# chart3.net
KiCad netlist of a schematic drawn in EAGLE
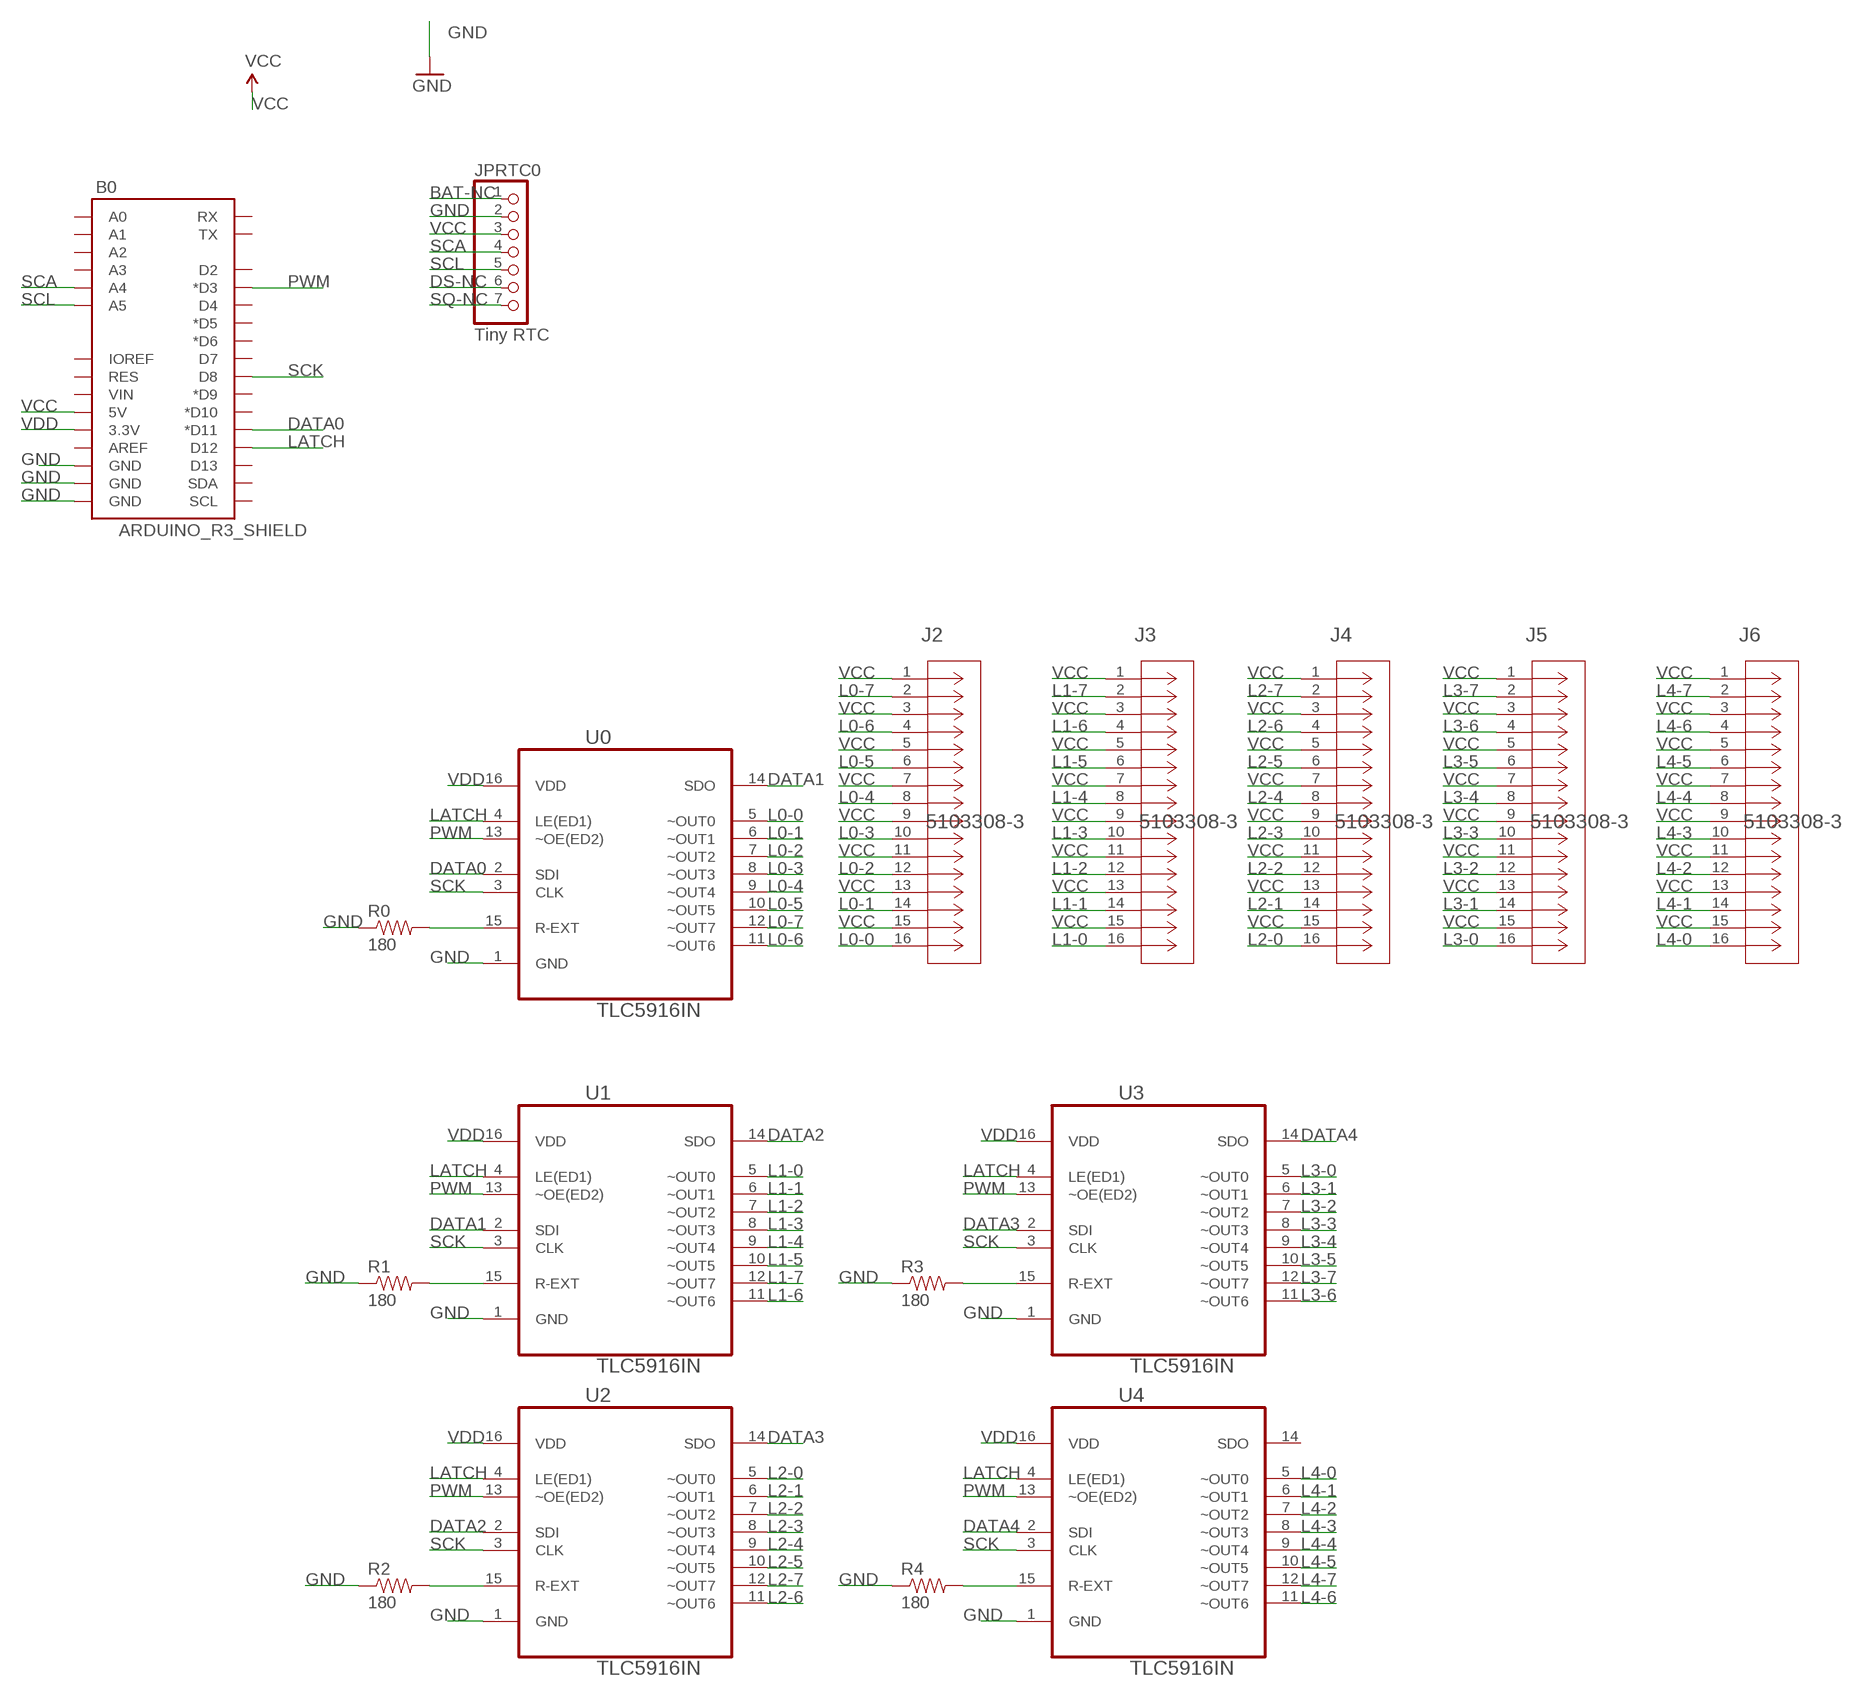
[diagram p0: schematic, sheet 1]

(export (version "E")
  (design (tool "Eeschema 10.0.6"))
  (components
    (comp (ref "B0")
      (value "ARDUINO_R3_SHIELD")
      (footprint "eagle-import:UNO_R3_SHIELD")
      (libsource (lib "eagle-import") (part "ARDUINO_R3_SHIELD"))
    )
    (comp (ref "J2")
      (value "5103308-3")
      (footprint "eagle-import:CON16_2X8_S4")
      (fields
        (field (name "DIGIKEYPARTNUMBER") "A33163-ND")
        (field (name "COPYRIGHT") "Copyright (C) 2015 Accelerated Designs. All rights reserved")
      )
      (libsource (lib "eagle-import") (part "5103308-3"))
    )
    (comp (ref "J3")
      (value "5103308-3")
      (footprint "eagle-import:CON16_2X8_S4")
      (fields
        (field (name "DIGIKEYPARTNUMBER") "A33163-ND")
        (field (name "COPYRIGHT") "Copyright (C) 2015 Accelerated Designs. All rights reserved")
      )
      (libsource (lib "eagle-import") (part "5103308-3"))
    )
    (comp (ref "J4")
      (value "5103308-3")
      (footprint "eagle-import:CON16_2X8_S4")
      (fields
        (field (name "DIGIKEYPARTNUMBER") "A33163-ND")
        (field (name "COPYRIGHT") "Copyright (C) 2015 Accelerated Designs. All rights reserved")
      )
      (libsource (lib "eagle-import") (part "5103308-3"))
    )
    (comp (ref "J5")
      (value "5103308-3")
      (footprint "eagle-import:CON16_2X8_S4")
      (fields
        (field (name "DIGIKEYPARTNUMBER") "A33163-ND")
        (field (name "COPYRIGHT") "Copyright (C) 2015 Accelerated Designs. All rights reserved")
      )
      (libsource (lib "eagle-import") (part "5103308-3"))
    )
    (comp (ref "J6")
      (value "5103308-3")
      (footprint "eagle-import:CON16_2X8_S4")
      (fields
        (field (name "DIGIKEYPARTNUMBER") "A33163-ND")
        (field (name "COPYRIGHT") "Copyright (C) 2015 Accelerated Designs. All rights reserved")
      )
      (libsource (lib "eagle-import") (part "5103308-3"))
    )
    (comp (ref "JPRTC0")
      (value "Tiny RTC")
      (footprint "eagle-import:1X07")
      (libsource (lib "eagle-import") (part "PINHD-1X7"))
    )
    (comp (ref "R0")
      (value "180")
      (footprint "eagle-import:AXIAL-0.4")
      (libsource (lib "eagle-import") (part "RESISTORPTH-1/4W"))
    )
    (comp (ref "R1")
      (value "180")
      (footprint "eagle-import:AXIAL-0.4")
      (libsource (lib "eagle-import") (part "RESISTORPTH-1/4W"))
    )
    (comp (ref "R2")
      (value "180")
      (footprint "eagle-import:AXIAL-0.4")
      (libsource (lib "eagle-import") (part "RESISTORPTH-1/4W"))
    )
    (comp (ref "R3")
      (value "180")
      (footprint "eagle-import:AXIAL-0.4")
      (libsource (lib "eagle-import") (part "RESISTORPTH-1/4W"))
    )
    (comp (ref "R4")
      (value "180")
      (footprint "eagle-import:AXIAL-0.4")
      (libsource (lib "eagle-import") (part "RESISTORPTH-1/4W"))
    )
    (comp (ref "U0")
      (value "TLC5916IN")
      (footprint "eagle-import:DIP254P762X508-16")
      (libsource (lib "eagle-import") (part "TLC5916IN"))
    )
    (comp (ref "U1")
      (value "TLC5916IN")
      (footprint "eagle-import:DIP254P762X508-16")
      (libsource (lib "eagle-import") (part "TLC5916IN"))
    )
    (comp (ref "U2")
      (value "TLC5916IN")
      (footprint "eagle-import:DIP254P762X508-16")
      (libsource (lib "eagle-import") (part "TLC5916IN"))
    )
    (comp (ref "U3")
      (value "TLC5916IN")
      (footprint "eagle-import:DIP254P762X508-16")
      (libsource (lib "eagle-import") (part "TLC5916IN"))
    )
    (comp (ref "U4")
      (value "TLC5916IN")
      (footprint "eagle-import:DIP254P762X508-16")
      (libsource (lib "eagle-import") (part "TLC5916IN"))
    )
  )
  (nets
    (net (code "1") (name "/BAT-NC") (class "Default")
      (node (ref "JPRTC0") (pin "1") (pinfunction "1_1") (pintype "passive"))
    )
    (net (code "2") (name "/DATA0") (class "Default")
      (node (ref "B0") (pin "D11") (pinfunction "*D11_D11") (pintype "bidirectional"))
      (node (ref "U0") (pin "2") (pinfunction "SDI_2") (pintype "input"))
    )
    (net (code "3") (name "/DATA1") (class "Default")
      (node (ref "U0") (pin "14") (pinfunction "SDO_14") (pintype "output"))
      (node (ref "U1") (pin "2") (pinfunction "SDI_2") (pintype "input"))
    )
    (net (code "4") (name "/DATA2") (class "Default")
      (node (ref "U1") (pin "14") (pinfunction "SDO_14") (pintype "output"))
      (node (ref "U2") (pin "2") (pinfunction "SDI_2") (pintype "input"))
    )
    (net (code "5") (name "/DATA3") (class "Default")
      (node (ref "U2") (pin "14") (pinfunction "SDO_14") (pintype "output"))
      (node (ref "U3") (pin "2") (pinfunction "SDI_2") (pintype "input"))
    )
    (net (code "6") (name "/DATA4") (class "Default")
      (node (ref "U3") (pin "14") (pinfunction "SDO_14") (pintype "output"))
      (node (ref "U4") (pin "2") (pinfunction "SDI_2") (pintype "input"))
    )
    (net (code "7") (name "/DS-NC") (class "Default")
      (node (ref "JPRTC0") (pin "6") (pinfunction "6_6") (pintype "passive"))
    )
    (net (code "8") (name "/L0-0") (class "Default")
      (node (ref "J2") (pin "16") (pinfunction "16_16") (pintype "passive"))
      (node (ref "U0") (pin "5") (pinfunction "~{OUT0}_5") (pintype "output"))
    )
    (net (code "9") (name "/L0-1") (class "Default")
      (node (ref "J2") (pin "14") (pinfunction "14_14") (pintype "passive"))
      (node (ref "U0") (pin "6") (pinfunction "~{OUT1}_6") (pintype "output"))
    )
    (net (code "10") (name "/L0-2") (class "Default")
      (node (ref "J2") (pin "12") (pinfunction "12_12") (pintype "passive"))
      (node (ref "U0") (pin "7") (pinfunction "~{OUT2}_7") (pintype "output"))
    )
    (net (code "11") (name "/L0-3") (class "Default")
      (node (ref "J2") (pin "10") (pinfunction "10_10") (pintype "passive"))
      (node (ref "U0") (pin "8") (pinfunction "~{OUT3}_8") (pintype "output"))
    )
    (net (code "12") (name "/L0-4") (class "Default")
      (node (ref "J2") (pin "8") (pinfunction "8_8") (pintype "passive"))
      (node (ref "U0") (pin "9") (pinfunction "~{OUT4}_9") (pintype "output"))
    )
    (net (code "13") (name "/L0-5") (class "Default")
      (node (ref "J2") (pin "6") (pinfunction "6_6") (pintype "passive"))
      (node (ref "U0") (pin "10") (pinfunction "~{OUT5}_10") (pintype "output"))
    )
    (net (code "14") (name "/L0-6") (class "Default")
      (node (ref "J2") (pin "4") (pinfunction "4_4") (pintype "passive"))
      (node (ref "U0") (pin "11") (pinfunction "~{OUT6}_11") (pintype "output"))
    )
    (net (code "15") (name "/L0-7") (class "Default")
      (node (ref "J2") (pin "2") (pinfunction "2_2") (pintype "passive"))
      (node (ref "U0") (pin "12") (pinfunction "~{OUT7}_12") (pintype "output"))
    )
    (net (code "16") (name "/L1-0") (class "Default")
      (node (ref "J3") (pin "16") (pinfunction "16_16") (pintype "passive"))
      (node (ref "U1") (pin "5") (pinfunction "~{OUT0}_5") (pintype "output"))
    )
    (net (code "17") (name "/L1-1") (class "Default")
      (node (ref "J3") (pin "14") (pinfunction "14_14") (pintype "passive"))
      (node (ref "U1") (pin "6") (pinfunction "~{OUT1}_6") (pintype "output"))
    )
    (net (code "18") (name "/L1-2") (class "Default")
      (node (ref "J3") (pin "12") (pinfunction "12_12") (pintype "passive"))
      (node (ref "U1") (pin "7") (pinfunction "~{OUT2}_7") (pintype "output"))
    )
    (net (code "19") (name "/L1-3") (class "Default")
      (node (ref "J3") (pin "10") (pinfunction "10_10") (pintype "passive"))
      (node (ref "U1") (pin "8") (pinfunction "~{OUT3}_8") (pintype "output"))
    )
    (net (code "20") (name "/L1-4") (class "Default")
      (node (ref "J3") (pin "8") (pinfunction "8_8") (pintype "passive"))
      (node (ref "U1") (pin "9") (pinfunction "~{OUT4}_9") (pintype "output"))
    )
    (net (code "21") (name "/L1-5") (class "Default")
      (node (ref "J3") (pin "6") (pinfunction "6_6") (pintype "passive"))
      (node (ref "U1") (pin "10") (pinfunction "~{OUT5}_10") (pintype "output"))
    )
    (net (code "22") (name "/L1-6") (class "Default")
      (node (ref "J3") (pin "4") (pinfunction "4_4") (pintype "passive"))
      (node (ref "U1") (pin "11") (pinfunction "~{OUT6}_11") (pintype "output"))
    )
    (net (code "23") (name "/L1-7") (class "Default")
      (node (ref "J3") (pin "2") (pinfunction "2_2") (pintype "passive"))
      (node (ref "U1") (pin "12") (pinfunction "~{OUT7}_12") (pintype "output"))
    )
    (net (code "24") (name "/L2-0") (class "Default")
      (node (ref "J4") (pin "16") (pinfunction "16_16") (pintype "passive"))
      (node (ref "U2") (pin "5") (pinfunction "~{OUT0}_5") (pintype "output"))
    )
    (net (code "25") (name "/L2-1") (class "Default")
      (node (ref "J4") (pin "14") (pinfunction "14_14") (pintype "passive"))
      (node (ref "U2") (pin "6") (pinfunction "~{OUT1}_6") (pintype "output"))
    )
    (net (code "26") (name "/L2-2") (class "Default")
      (node (ref "J4") (pin "12") (pinfunction "12_12") (pintype "passive"))
      (node (ref "U2") (pin "7") (pinfunction "~{OUT2}_7") (pintype "output"))
    )
    (net (code "27") (name "/L2-3") (class "Default")
      (node (ref "J4") (pin "10") (pinfunction "10_10") (pintype "passive"))
      (node (ref "U2") (pin "8") (pinfunction "~{OUT3}_8") (pintype "output"))
    )
    (net (code "28") (name "/L2-4") (class "Default")
      (node (ref "J4") (pin "8") (pinfunction "8_8") (pintype "passive"))
      (node (ref "U2") (pin "9") (pinfunction "~{OUT4}_9") (pintype "output"))
    )
    (net (code "29") (name "/L2-5") (class "Default")
      (node (ref "J4") (pin "6") (pinfunction "6_6") (pintype "passive"))
      (node (ref "U2") (pin "10") (pinfunction "~{OUT5}_10") (pintype "output"))
    )
    (net (code "30") (name "/L2-6") (class "Default")
      (node (ref "J4") (pin "4") (pinfunction "4_4") (pintype "passive"))
      (node (ref "U2") (pin "11") (pinfunction "~{OUT6}_11") (pintype "output"))
    )
    (net (code "31") (name "/L2-7") (class "Default")
      (node (ref "J4") (pin "2") (pinfunction "2_2") (pintype "passive"))
      (node (ref "U2") (pin "12") (pinfunction "~{OUT7}_12") (pintype "output"))
    )
    (net (code "32") (name "/L3-0") (class "Default")
      (node (ref "J5") (pin "16") (pinfunction "16_16") (pintype "passive"))
      (node (ref "U3") (pin "5") (pinfunction "~{OUT0}_5") (pintype "output"))
    )
    (net (code "33") (name "/L3-1") (class "Default")
      (node (ref "J5") (pin "14") (pinfunction "14_14") (pintype "passive"))
      (node (ref "U3") (pin "6") (pinfunction "~{OUT1}_6") (pintype "output"))
    )
    (net (code "34") (name "/L3-2") (class "Default")
      (node (ref "J5") (pin "12") (pinfunction "12_12") (pintype "passive"))
      (node (ref "U3") (pin "7") (pinfunction "~{OUT2}_7") (pintype "output"))
    )
    (net (code "35") (name "/L3-3") (class "Default")
      (node (ref "J5") (pin "10") (pinfunction "10_10") (pintype "passive"))
      (node (ref "U3") (pin "8") (pinfunction "~{OUT3}_8") (pintype "output"))
    )
    (net (code "36") (name "/L3-4") (class "Default")
      (node (ref "J5") (pin "8") (pinfunction "8_8") (pintype "passive"))
      (node (ref "U3") (pin "9") (pinfunction "~{OUT4}_9") (pintype "output"))
    )
    (net (code "37") (name "/L3-5") (class "Default")
      (node (ref "J5") (pin "6") (pinfunction "6_6") (pintype "passive"))
      (node (ref "U3") (pin "10") (pinfunction "~{OUT5}_10") (pintype "output"))
    )
    (net (code "38") (name "/L3-6") (class "Default")
      (node (ref "J5") (pin "4") (pinfunction "4_4") (pintype "passive"))
      (node (ref "U3") (pin "11") (pinfunction "~{OUT6}_11") (pintype "output"))
    )
    (net (code "39") (name "/L3-7") (class "Default")
      (node (ref "J5") (pin "2") (pinfunction "2_2") (pintype "passive"))
      (node (ref "U3") (pin "12") (pinfunction "~{OUT7}_12") (pintype "output"))
    )
    (net (code "40") (name "/L4-0") (class "Default")
      (node (ref "J6") (pin "16") (pinfunction "16_16") (pintype "passive"))
      (node (ref "U4") (pin "5") (pinfunction "~{OUT0}_5") (pintype "output"))
    )
    (net (code "41") (name "/L4-1") (class "Default")
      (node (ref "J6") (pin "14") (pinfunction "14_14") (pintype "passive"))
      (node (ref "U4") (pin "6") (pinfunction "~{OUT1}_6") (pintype "output"))
    )
    (net (code "42") (name "/L4-2") (class "Default")
      (node (ref "J6") (pin "12") (pinfunction "12_12") (pintype "passive"))
      (node (ref "U4") (pin "7") (pinfunction "~{OUT2}_7") (pintype "output"))
    )
    (net (code "43") (name "/L4-3") (class "Default")
      (node (ref "J6") (pin "10") (pinfunction "10_10") (pintype "passive"))
      (node (ref "U4") (pin "8") (pinfunction "~{OUT3}_8") (pintype "output"))
    )
    (net (code "44") (name "/L4-4") (class "Default")
      (node (ref "J6") (pin "8") (pinfunction "8_8") (pintype "passive"))
      (node (ref "U4") (pin "9") (pinfunction "~{OUT4}_9") (pintype "output"))
    )
    (net (code "45") (name "/L4-5") (class "Default")
      (node (ref "J6") (pin "6") (pinfunction "6_6") (pintype "passive"))
      (node (ref "U4") (pin "10") (pinfunction "~{OUT5}_10") (pintype "output"))
    )
    (net (code "46") (name "/L4-6") (class "Default")
      (node (ref "J6") (pin "4") (pinfunction "4_4") (pintype "passive"))
      (node (ref "U4") (pin "11") (pinfunction "~{OUT6}_11") (pintype "output"))
    )
    (net (code "47") (name "/L4-7") (class "Default")
      (node (ref "J6") (pin "2") (pinfunction "2_2") (pintype "passive"))
      (node (ref "U4") (pin "12") (pinfunction "~{OUT7}_12") (pintype "output"))
    )
    (net (code "48") (name "/LATCH") (class "Default")
      (node (ref "B0") (pin "D12") (pinfunction "D12_D12") (pintype "bidirectional"))
      (node (ref "U0") (pin "4") (pinfunction "LE(ED1)_4") (pintype "input"))
      (node (ref "U1") (pin "4") (pinfunction "LE(ED1)_4") (pintype "input"))
      (node (ref "U2") (pin "4") (pinfunction "LE(ED1)_4") (pintype "input"))
      (node (ref "U3") (pin "4") (pinfunction "LE(ED1)_4") (pintype "input"))
      (node (ref "U4") (pin "4") (pinfunction "LE(ED1)_4") (pintype "input"))
    )
    (net (code "49") (name "/PWM") (class "Default")
      (node (ref "B0") (pin "D3") (pinfunction "*D3_D3") (pintype "bidirectional"))
      (node (ref "U0") (pin "13") (pinfunction "~{OE(ED2})_13") (pintype "input"))
      (node (ref "U1") (pin "13") (pinfunction "~{OE(ED2})_13") (pintype "input"))
      (node (ref "U2") (pin "13") (pinfunction "~{OE(ED2})_13") (pintype "input"))
      (node (ref "U3") (pin "13") (pinfunction "~{OE(ED2})_13") (pintype "input"))
      (node (ref "U4") (pin "13") (pinfunction "~{OE(ED2})_13") (pintype "input"))
    )
    (net (code "50") (name "/SCA") (class "Default")
      (node (ref "B0") (pin "A4") (pinfunction "A4_A4") (pintype "bidirectional"))
      (node (ref "JPRTC0") (pin "4") (pinfunction "4_4") (pintype "passive"))
    )
    (net (code "51") (name "/SCK") (class "Default")
      (node (ref "B0") (pin "D8") (pinfunction "D8_D8") (pintype "bidirectional"))
      (node (ref "U0") (pin "3") (pinfunction "CLK_3") (pintype "input"))
      (node (ref "U1") (pin "3") (pinfunction "CLK_3") (pintype "input"))
      (node (ref "U2") (pin "3") (pinfunction "CLK_3") (pintype "input"))
      (node (ref "U3") (pin "3") (pinfunction "CLK_3") (pintype "input"))
      (node (ref "U4") (pin "3") (pinfunction "CLK_3") (pintype "input"))
    )
    (net (code "52") (name "/SCL") (class "Default")
      (node (ref "B0") (pin "A5") (pinfunction "A5_A5") (pintype "bidirectional"))
      (node (ref "JPRTC0") (pin "5") (pinfunction "5_5") (pintype "passive"))
    )
    (net (code "53") (name "/SQ-NC") (class "Default")
      (node (ref "JPRTC0") (pin "7") (pinfunction "7_7") (pintype "passive"))
    )
    (net (code "54") (name "/VDD") (class "Default")
      (node (ref "B0") (pin "3.3V") (pinfunction "3.3V_3.3V") (pintype "bidirectional"))
      (node (ref "U0") (pin "16") (pinfunction "VDD_16") (pintype "power_in"))
      (node (ref "U1") (pin "16") (pinfunction "VDD_16") (pintype "power_in"))
      (node (ref "U2") (pin "16") (pinfunction "VDD_16") (pintype "power_in"))
      (node (ref "U3") (pin "16") (pinfunction "VDD_16") (pintype "power_in"))
      (node (ref "U4") (pin "16") (pinfunction "VDD_16") (pintype "power_in"))
    )
    (net (code "55") (name "GND") (class "Default")
      (node (ref "B0") (pin "GND@0") (pinfunction "GND_GND@0") (pintype "bidirectional"))
      (node (ref "B0") (pin "GND@1") (pinfunction "GND_GND@1") (pintype "bidirectional"))
      (node (ref "B0") (pin "GND@2") (pinfunction "GND_GND@2") (pintype "bidirectional"))
      (node (ref "JPRTC0") (pin "2") (pinfunction "2_2") (pintype "passive"))
      (node (ref "R0") (pin "P$1") (pinfunction "1_P$1") (pintype "passive"))
      (node (ref "R1") (pin "P$1") (pinfunction "1_P$1") (pintype "passive"))
      (node (ref "R2") (pin "P$1") (pinfunction "1_P$1") (pintype "passive"))
      (node (ref "R3") (pin "P$1") (pinfunction "1_P$1") (pintype "passive"))
      (node (ref "R4") (pin "P$1") (pinfunction "1_P$1") (pintype "passive"))
      (node (ref "U0") (pin "1") (pinfunction "GND_1") (pintype "passive"))
      (node (ref "U1") (pin "1") (pinfunction "GND_1") (pintype "passive"))
      (node (ref "U2") (pin "1") (pinfunction "GND_1") (pintype "passive"))
      (node (ref "U3") (pin "1") (pinfunction "GND_1") (pintype "passive"))
      (node (ref "U4") (pin "1") (pinfunction "GND_1") (pintype "passive"))
    )
    (net (code "56") (name "Net-(R0-2)") (class "Default")
      (node (ref "R0") (pin "P$2") (pinfunction "2_P$2") (pintype "passive"))
      (node (ref "U0") (pin "15") (pinfunction "R-EXT_15") (pintype "passive"))
    )
    (net (code "57") (name "Net-(R1-2)") (class "Default")
      (node (ref "R1") (pin "P$2") (pinfunction "2_P$2") (pintype "passive"))
      (node (ref "U1") (pin "15") (pinfunction "R-EXT_15") (pintype "passive"))
    )
    (net (code "58") (name "Net-(R2-2)") (class "Default")
      (node (ref "R2") (pin "P$2") (pinfunction "2_P$2") (pintype "passive"))
      (node (ref "U2") (pin "15") (pinfunction "R-EXT_15") (pintype "passive"))
    )
    (net (code "59") (name "Net-(R3-2)") (class "Default")
      (node (ref "R3") (pin "P$2") (pinfunction "2_P$2") (pintype "passive"))
      (node (ref "U3") (pin "15") (pinfunction "R-EXT_15") (pintype "passive"))
    )
    (net (code "60") (name "Net-(R4-2)") (class "Default")
      (node (ref "R4") (pin "P$2") (pinfunction "2_P$2") (pintype "passive"))
      (node (ref "U4") (pin "15") (pinfunction "R-EXT_15") (pintype "passive"))
    )
    (net (code "61") (name "VCC") (class "Default")
      (node (ref "B0") (pin "5V") (pinfunction "5V_5V") (pintype "bidirectional"))
      (node (ref "J2") (pin "1") (pinfunction "1_1") (pintype "passive"))
      (node (ref "J2") (pin "11") (pinfunction "11_11") (pintype "passive"))
      (node (ref "J2") (pin "13") (pinfunction "13_13") (pintype "passive"))
      (node (ref "J2") (pin "15") (pinfunction "15_15") (pintype "passive"))
      (node (ref "J2") (pin "3") (pinfunction "3_3") (pintype "passive"))
      (node (ref "J2") (pin "5") (pinfunction "5_5") (pintype "passive"))
      (node (ref "J2") (pin "7") (pinfunction "7_7") (pintype "passive"))
      (node (ref "J2") (pin "9") (pinfunction "9_9") (pintype "passive"))
      (node (ref "J3") (pin "1") (pinfunction "1_1") (pintype "passive"))
      (node (ref "J3") (pin "11") (pinfunction "11_11") (pintype "passive"))
      (node (ref "J3") (pin "13") (pinfunction "13_13") (pintype "passive"))
      (node (ref "J3") (pin "15") (pinfunction "15_15") (pintype "passive"))
      (node (ref "J3") (pin "3") (pinfunction "3_3") (pintype "passive"))
      (node (ref "J3") (pin "5") (pinfunction "5_5") (pintype "passive"))
      (node (ref "J3") (pin "7") (pinfunction "7_7") (pintype "passive"))
      (node (ref "J3") (pin "9") (pinfunction "9_9") (pintype "passive"))
      (node (ref "J4") (pin "1") (pinfunction "1_1") (pintype "passive"))
      (node (ref "J4") (pin "11") (pinfunction "11_11") (pintype "passive"))
      (node (ref "J4") (pin "13") (pinfunction "13_13") (pintype "passive"))
      (node (ref "J4") (pin "15") (pinfunction "15_15") (pintype "passive"))
      (node (ref "J4") (pin "3") (pinfunction "3_3") (pintype "passive"))
      (node (ref "J4") (pin "5") (pinfunction "5_5") (pintype "passive"))
      (node (ref "J4") (pin "7") (pinfunction "7_7") (pintype "passive"))
      (node (ref "J4") (pin "9") (pinfunction "9_9") (pintype "passive"))
      (node (ref "J5") (pin "1") (pinfunction "1_1") (pintype "passive"))
      (node (ref "J5") (pin "11") (pinfunction "11_11") (pintype "passive"))
      (node (ref "J5") (pin "13") (pinfunction "13_13") (pintype "passive"))
      (node (ref "J5") (pin "15") (pinfunction "15_15") (pintype "passive"))
      (node (ref "J5") (pin "3") (pinfunction "3_3") (pintype "passive"))
      (node (ref "J5") (pin "5") (pinfunction "5_5") (pintype "passive"))
      (node (ref "J5") (pin "7") (pinfunction "7_7") (pintype "passive"))
      (node (ref "J5") (pin "9") (pinfunction "9_9") (pintype "passive"))
      (node (ref "J6") (pin "1") (pinfunction "1_1") (pintype "passive"))
      (node (ref "J6") (pin "11") (pinfunction "11_11") (pintype "passive"))
      (node (ref "J6") (pin "13") (pinfunction "13_13") (pintype "passive"))
      (node (ref "J6") (pin "15") (pinfunction "15_15") (pintype "passive"))
      (node (ref "J6") (pin "3") (pinfunction "3_3") (pintype "passive"))
      (node (ref "J6") (pin "5") (pinfunction "5_5") (pintype "passive"))
      (node (ref "J6") (pin "7") (pinfunction "7_7") (pintype "passive"))
      (node (ref "J6") (pin "9") (pinfunction "9_9") (pintype "passive"))
      (node (ref "JPRTC0") (pin "3") (pinfunction "3_3") (pintype "passive"))
    )
    (net (code "62") (name "unconnected-(B0-*D5-PadD5)") (class "Default")
      (node (ref "B0") (pin "D5") (pinfunction "*D5_D5") (pintype "bidirectional"))
    )
    (net (code "63") (name "unconnected-(B0-*D6-PadD6)") (class "Default")
      (node (ref "B0") (pin "D6") (pinfunction "*D6_D6") (pintype "bidirectional"))
    )
    (net (code "64") (name "unconnected-(B0-*D9-PadD9)") (class "Default")
      (node (ref "B0") (pin "D9") (pinfunction "*D9_D9") (pintype "bidirectional"))
    )
    (net (code "65") (name "unconnected-(B0-*D10-PadD10)") (class "Default")
      (node (ref "B0") (pin "D10") (pinfunction "*D10_D10") (pintype "bidirectional"))
    )
    (net (code "66") (name "unconnected-(B0-PadA0)") (class "Default")
      (node (ref "B0") (pin "A0") (pinfunction "A0_A0") (pintype "bidirectional"))
    )
    (net (code "67") (name "unconnected-(B0-PadA1)") (class "Default")
      (node (ref "B0") (pin "A1") (pinfunction "A1_A1") (pintype "bidirectional"))
    )
    (net (code "68") (name "unconnected-(B0-PadA2)") (class "Default")
      (node (ref "B0") (pin "A2") (pinfunction "A2_A2") (pintype "bidirectional"))
    )
    (net (code "69") (name "unconnected-(B0-PadA3)") (class "Default")
      (node (ref "B0") (pin "A3") (pinfunction "A3_A3") (pintype "bidirectional"))
    )
    (net (code "70") (name "unconnected-(B0-PadAREF)") (class "Default")
      (node (ref "B0") (pin "AREF") (pinfunction "AREF_AREF") (pintype "bidirectional"))
    )
    (net (code "71") (name "unconnected-(B0-PadD2)") (class "Default")
      (node (ref "B0") (pin "D2") (pinfunction "D2_D2") (pintype "bidirectional"))
    )
    (net (code "72") (name "unconnected-(B0-PadD4)") (class "Default")
      (node (ref "B0") (pin "D4") (pinfunction "D4_D4") (pintype "bidirectional"))
    )
    (net (code "73") (name "unconnected-(B0-PadD7)") (class "Default")
      (node (ref "B0") (pin "D7") (pinfunction "D7_D7") (pintype "bidirectional"))
    )
    (net (code "74") (name "unconnected-(B0-PadD13)") (class "Default")
      (node (ref "B0") (pin "D13") (pinfunction "D13_D13") (pintype "bidirectional"))
    )
    (net (code "75") (name "unconnected-(B0-PadIOREF)") (class "Default")
      (node (ref "B0") (pin "IOREF") (pinfunction "IOREF_IOREF") (pintype "bidirectional"))
    )
    (net (code "76") (name "unconnected-(B0-PadRES)") (class "Default")
      (node (ref "B0") (pin "RES") (pinfunction "RES_RES") (pintype "bidirectional"))
    )
    (net (code "77") (name "unconnected-(B0-PadRX)") (class "Default")
      (node (ref "B0") (pin "RX") (pinfunction "RX_RX") (pintype "bidirectional"))
    )
    (net (code "78") (name "unconnected-(B0-PadSCL)") (class "Default")
      (node (ref "B0") (pin "SCL") (pinfunction "SCL_SCL") (pintype "bidirectional"))
    )
    (net (code "79") (name "unconnected-(B0-PadSDA)") (class "Default")
      (node (ref "B0") (pin "SDA") (pinfunction "SDA_SDA") (pintype "bidirectional"))
    )
    (net (code "80") (name "unconnected-(B0-PadTX)") (class "Default")
      (node (ref "B0") (pin "TX") (pinfunction "TX_TX") (pintype "bidirectional"))
    )
    (net (code "81") (name "unconnected-(B0-PadVIN)") (class "Default")
      (node (ref "B0") (pin "VIN") (pinfunction "VIN_VIN") (pintype "bidirectional"))
    )
    (net (code "82") (name "unconnected-(U4-SDO-Pad14)") (class "Default")
      (node (ref "U4") (pin "14") (pinfunction "SDO_14") (pintype "output"))
    )
  )
)
